# Universalsensor.net
KiCad netlist of a schematic drawn in EAGLE
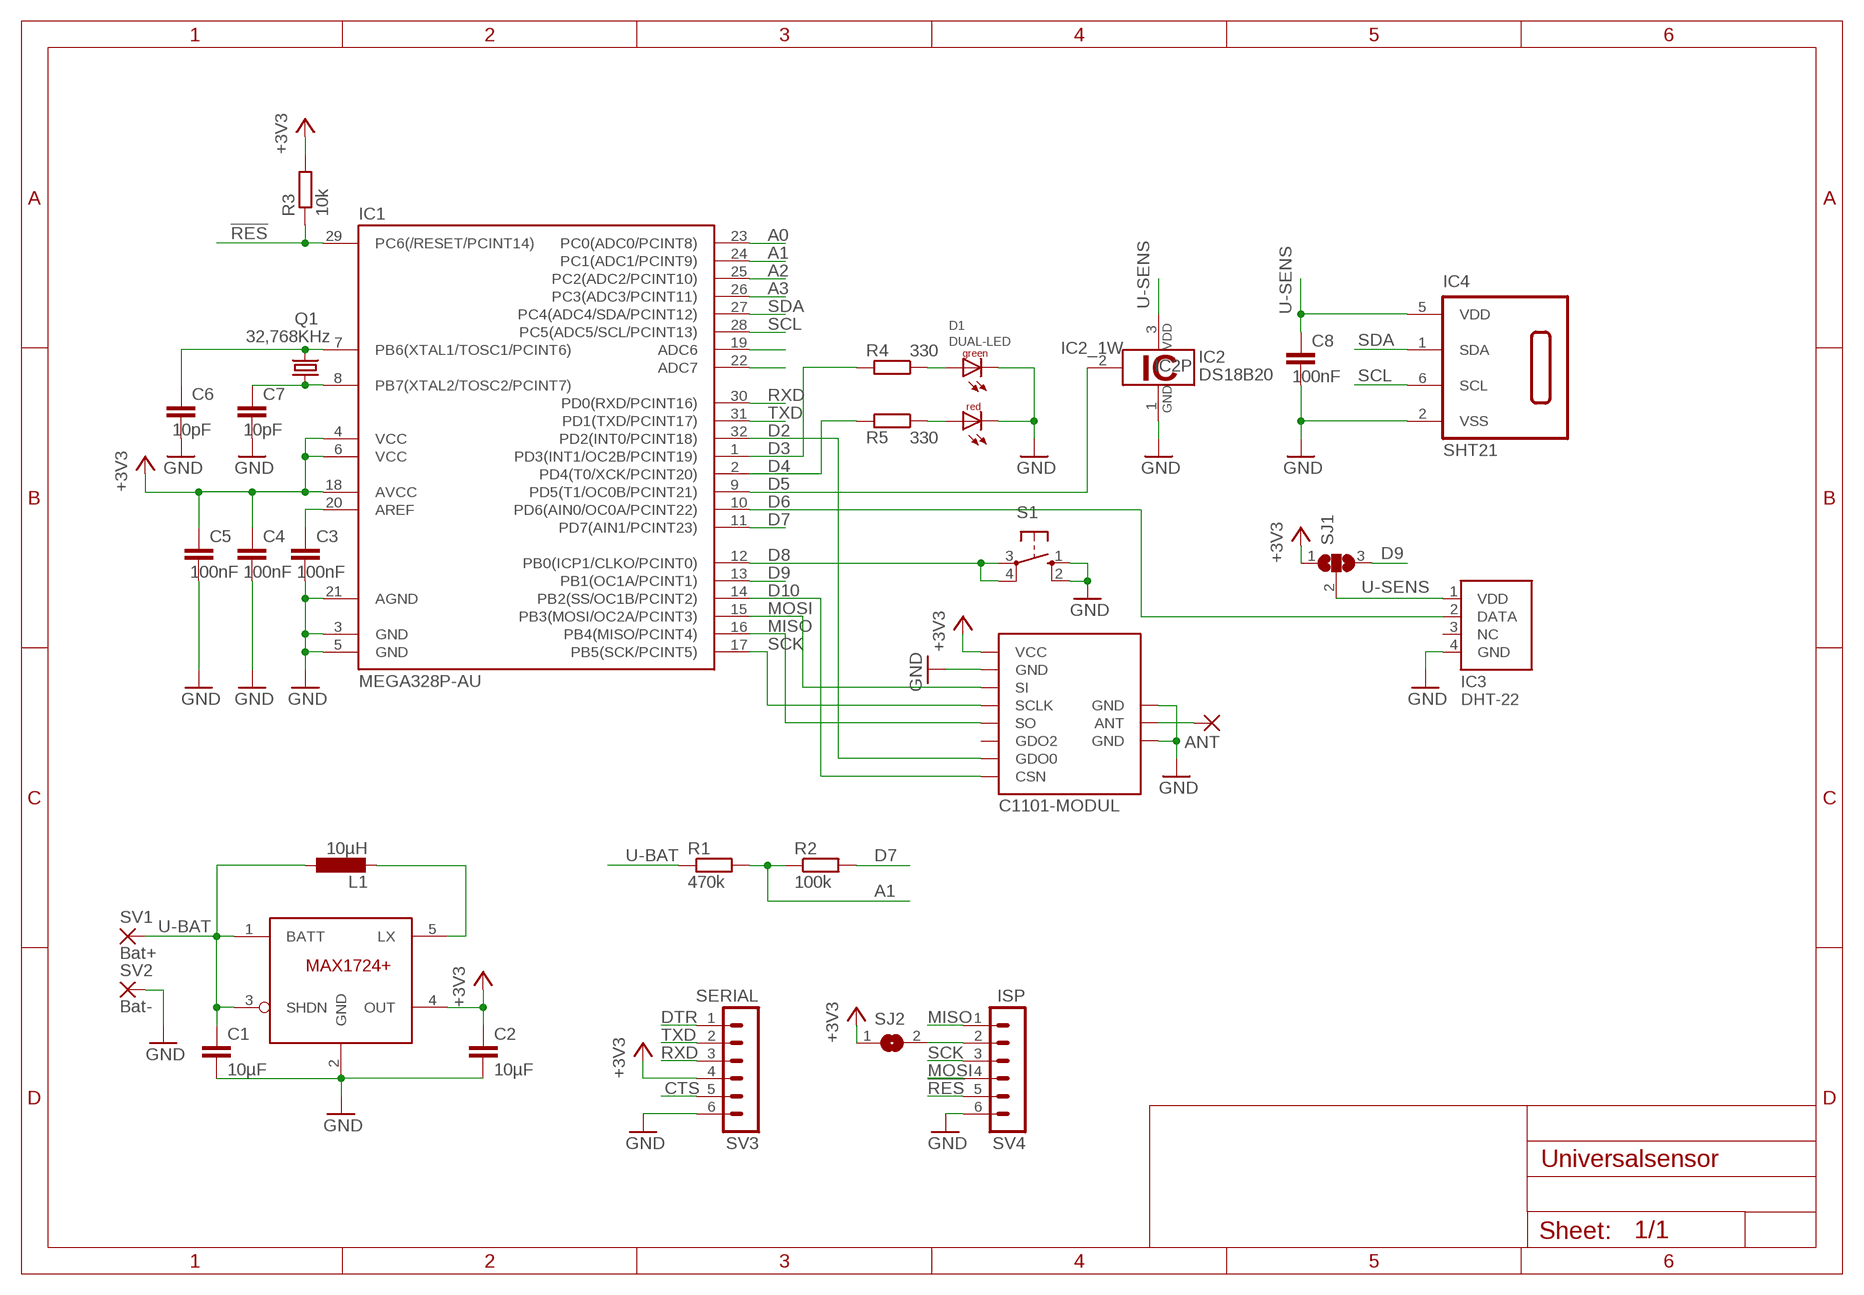
[diagram p0: schematic, sheet 1]

(export (version "E")
  (design (tool "Eeschema 10.0.6"))
  (components
    (comp (ref "ANT")
      (value "2,54/1,1")
      (footprint "eagle-import:2,54_1,1")
      (libsource (lib "eagle-import") (part "2,54/1,1"))
    )
    (comp (ref "C1")
      (value "10µF")
      (footprint "eagle-import:C0603K")
      (libsource (lib "eagle-import") (part "C-EUC0603K"))
    )
    (comp (ref "C2")
      (value "10µF")
      (footprint "eagle-import:C0603K")
      (libsource (lib "eagle-import") (part "C-EUC0603K"))
    )
    (comp (ref "C3")
      (value "100nF")
      (footprint "eagle-import:C0603K")
      (libsource (lib "eagle-import") (part "C-EUC0603K"))
    )
    (comp (ref "C4")
      (value "100nF")
      (footprint "eagle-import:C0603K")
      (libsource (lib "eagle-import") (part "C-EUC0603K"))
    )
    (comp (ref "C5")
      (value "100nF")
      (footprint "eagle-import:C0603K")
      (libsource (lib "eagle-import") (part "C-EUC0603K"))
    )
    (comp (ref "C6")
      (value "10pF")
      (footprint "eagle-import:C0603K")
      (libsource (lib "eagle-import") (part "C-EUC0603K"))
    )
    (comp (ref "C7")
      (value "10pF")
      (footprint "eagle-import:C0603K")
      (libsource (lib "eagle-import") (part "C-EUC0603K"))
    )
    (comp (ref "C8")
      (value "100nF")
      (footprint "eagle-import:C0603K")
      (libsource (lib "eagle-import") (part "C-EUC0603K"))
    )
    (comp (ref "D1")
      (value "DUAL-LED")
      (footprint "eagle-import:DUAL-LED")
      (libsource (lib "eagle-import") (part "DUAL-LED"))
    )
    (comp (ref "IC1")
      (value "MEGA328P-AU")
      (footprint "eagle-import:TQFP32-08")
      (libsource (lib "eagle-import") (part "MEGA48/88/168-AU"))
    )
    (comp (ref "IC2")
      (value "DS18B20")
      (footprint "eagle-import:TO92-")
      (libsource (lib "eagle-import") (part "DS18B20"))
    )
    (comp (ref "IC3")
      (value "DHT-22")
      (footprint "eagle-import:DHT-22-L")
      (libsource (lib "eagle-import") (part "DHT-22"))
    )
    (comp (ref "IC4")
      (value "SHT21")
      (footprint "eagle-import:DFN6_SHT")
      (libsource (lib "eagle-import") (part "SHT21"))
    )
    (comp (ref "IC5")
      (value "MAX1724")
      (footprint "eagle-import:SOT23-5L")
      (libsource (lib "eagle-import") (part "MAX1724"))
    )
    (comp (ref "L1")
      (value "10µH")
      (footprint "eagle-import:L3230M")
      (libsource (lib "eagle-import") (part "L-EUL3230M"))
    )
    (comp (ref "Q1")
      (value "32,768KHz")
      (footprint "eagle-import:OSCILLATOR_SMD")
      (libsource (lib "eagle-import") (part "OSCILLATOR_32KHZ"))
    )
    (comp (ref "R1")
      (value "470k")
      (footprint "eagle-import:R0805")
      (libsource (lib "eagle-import") (part "R-EU_R0805"))
    )
    (comp (ref "R2")
      (value "100k")
      (footprint "eagle-import:R0805")
      (libsource (lib "eagle-import") (part "R-EU_R0805"))
    )
    (comp (ref "R3")
      (value "10k")
      (footprint "eagle-import:R0805")
      (libsource (lib "eagle-import") (part "R-EU_R0805"))
    )
    (comp (ref "R4")
      (value "330")
      (footprint "eagle-import:R0805")
      (libsource (lib "eagle-import") (part "R-EU_R0805"))
    )
    (comp (ref "R5")
      (value "330")
      (footprint "eagle-import:R0805")
      (libsource (lib "eagle-import") (part "R-EU_R0805"))
    )
    (comp (ref "S1")
      (value "10-XX")
      (footprint "eagle-import:B3F-10XX")
      (fields (field (name "MPN") "B3F-1000"))
      (libsource (lib "eagle-import") (part "10-XX"))
    )
    (comp (ref "SJ1")
      (value "SJ2W")
      (footprint "eagle-import:SJ_2")
      (libsource (lib "eagle-import") (part "SJ2W"))
    )
    (comp (ref "SJ2") (value "SJ") (footprint "eagle-import:SJ") (libsource (lib "eagle-import") (part "SJ")))
    (comp (ref "SV1")
      (value "Bat+")
      (footprint "eagle-import:2,54_1,1")
      (libsource (lib "eagle-import") (part "2,54/1,1"))
    )
    (comp (ref "SV2")
      (value "Bat-")
      (footprint "eagle-import:2,54_1,1")
      (libsource (lib "eagle-import") (part "2,54/1,1"))
    )
    (comp (ref "SV3")
      (value "SERIAL")
      (footprint "eagle-import:MA06-1")
      (libsource (lib "eagle-import") (part "MA06-1"))
    )
    (comp (ref "SV4")
      (value "ISP")
      (footprint "eagle-import:MA06-1")
      (libsource (lib "eagle-import") (part "MA06-1"))
    )
    (comp (ref "U$2")
      (value "C1101-MODUL")
      (footprint "eagle-import:CC1101-MODUL")
      (libsource (lib "eagle-import") (part "C1101-MODUL"))
    )
  )
  (nets
    (net (code "1") (name "+3V3") (class "Default")
      (node (ref "C2") (pin "1") (pinfunction "1_1") (pintype "passive"))
      (node (ref "C4") (pin "1") (pinfunction "1_1") (pintype "passive"))
      (node (ref "C5") (pin "1") (pinfunction "1_1") (pintype "passive"))
      (node (ref "IC1") (pin "18") (pinfunction "AVCC_18") (pintype "passive"))
      (node (ref "IC1") (pin "4") (pinfunction "VCC_4") (pintype "power_in"))
      (node (ref "IC1") (pin "6") (pinfunction "VCC_6") (pintype "power_in"))
      (node (ref "IC5") (pin "4") (pinfunction "OUT_4") (pintype "output"))
      (node (ref "R3") (pin "2") (pinfunction "2_2") (pintype "passive"))
      (node (ref "SJ1") (pin "1") (pinfunction "1_1") (pintype "passive"))
      (node (ref "SJ2") (pin "1") (pinfunction "1_1") (pintype "passive"))
      (node (ref "SV3") (pin "4") (pinfunction "4_4") (pintype "passive"))
      (node (ref "U$2") (pin "VCC") (pinfunction "VCC_VCC") (pintype "power_in"))
    )
    (net (code "2") (name "/A0") (class "Default")
      (node (ref "IC1") (pin "23") (pinfunction "PC0(ADC0/PCINT8)_23") (pintype "bidirectional"))
    )
    (net (code "3") (name "/A1") (class "Default")
      (node (ref "IC1") (pin "24") (pinfunction "PC1(ADC1/PCINT9)_24") (pintype "bidirectional"))
      (node (ref "R1") (pin "2") (pinfunction "2_2") (pintype "passive"))
      (node (ref "R2") (pin "1") (pinfunction "1_1") (pintype "passive"))
    )
    (net (code "4") (name "/A2") (class "Default")
      (node (ref "IC1") (pin "25") (pinfunction "PC2(ADC2/PCINT10)_25") (pintype "bidirectional"))
    )
    (net (code "5") (name "/A3") (class "Default")
      (node (ref "IC1") (pin "26") (pinfunction "PC3(ADC3/PCINT11)_26") (pintype "bidirectional"))
    )
    (net (code "6") (name "/CTS") (class "Default")
      (node (ref "SV3") (pin "5") (pinfunction "5_5") (pintype "passive"))
    )
    (net (code "7") (name "/D2") (class "Default")
      (node (ref "IC1") (pin "32") (pinfunction "PD2(INT0/PCINT18)_32") (pintype "bidirectional"))
      (node (ref "U$2") (pin "GDO0") (pinfunction "GDO0_GDO0") (pintype "bidirectional"))
    )
    (net (code "8") (name "/D3") (class "Default")
      (node (ref "IC1") (pin "1") (pinfunction "PD3(INT1/OC2B/PCINT19)_1") (pintype "bidirectional"))
      (node (ref "R4") (pin "2") (pinfunction "2_2") (pintype "passive"))
    )
    (net (code "9") (name "/D4") (class "Default")
      (node (ref "IC1") (pin "2") (pinfunction "PD4(T0/XCK/PCINT20)_2") (pintype "bidirectional"))
      (node (ref "R5") (pin "2") (pinfunction "2_2") (pintype "passive"))
    )
    (net (code "10") (name "/D5") (class "Default")
      (node (ref "IC1") (pin "9") (pinfunction "PD5(T1/OC0B/PCINT21)_9") (pintype "bidirectional"))
      (node (ref "IC2") (pin "2") (pinfunction "1W_2") (pintype "power_in"))
    )
    (net (code "11") (name "/D6") (class "Default")
      (node (ref "IC1") (pin "10") (pinfunction "PD6(AIN0/OC0A/PCINT22)_10") (pintype "bidirectional"))
      (node (ref "IC3") (pin "2") (pinfunction "DATA_2") (pintype "bidirectional"))
    )
    (net (code "12") (name "/D7") (class "Default")
      (node (ref "IC1") (pin "11") (pinfunction "PD7(AIN1/PCINT23)_11") (pintype "bidirectional"))
      (node (ref "R2") (pin "2") (pinfunction "2_2") (pintype "passive"))
    )
    (net (code "13") (name "/D8") (class "Default")
      (node (ref "IC1") (pin "12") (pinfunction "PB0(ICP1/CLKO/PCINT0)_12") (pintype "bidirectional"))
      (node (ref "S1") (pin "3") (pinfunction "P_3") (pintype "passive"))
      (node (ref "S1") (pin "4") (pinfunction "P1_4") (pintype "passive"))
    )
    (net (code "14") (name "/D9") (class "Default")
      (node (ref "IC1") (pin "13") (pinfunction "PB1(OC1A/PCINT1)_13") (pintype "bidirectional"))
      (node (ref "SJ1") (pin "3") (pinfunction "3_3") (pintype "passive"))
    )
    (net (code "15") (name "/D10") (class "Default")
      (node (ref "IC1") (pin "14") (pinfunction "PB2(SS/OC1B/PCINT2)_14") (pintype "bidirectional"))
      (node (ref "U$2") (pin "CSN") (pinfunction "CSN_CSN") (pintype "bidirectional"))
    )
    (net (code "16") (name "/DTR") (class "Default")
      (node (ref "SV3") (pin "1") (pinfunction "1_1") (pintype "passive"))
    )
    (net (code "17") (name "/MISO") (class "Default")
      (node (ref "IC1") (pin "16") (pinfunction "PB4(MISO/PCINT4)_16") (pintype "bidirectional"))
      (node (ref "SV4") (pin "1") (pinfunction "1_1") (pintype "passive"))
      (node (ref "U$2") (pin "SO") (pinfunction "SO_SO") (pintype "bidirectional"))
    )
    (net (code "18") (name "/MOSI") (class "Default")
      (node (ref "IC1") (pin "15") (pinfunction "PB3(MOSI/OC2A/PCINT3)_15") (pintype "bidirectional"))
      (node (ref "SV4") (pin "4") (pinfunction "4_4") (pintype "passive"))
      (node (ref "U$2") (pin "SI") (pinfunction "SI_SI") (pintype "bidirectional"))
    )
    (net (code "19") (name "/RXD") (class "Default")
      (node (ref "IC1") (pin "30") (pinfunction "PD0(RXD/PCINT16)_30") (pintype "bidirectional"))
      (node (ref "SV3") (pin "3") (pinfunction "3_3") (pintype "passive"))
    )
    (net (code "20") (name "/SCK") (class "Default")
      (node (ref "IC1") (pin "17") (pinfunction "PB5(SCK/PCINT5)_17") (pintype "bidirectional"))
      (node (ref "SV4") (pin "3") (pinfunction "3_3") (pintype "passive"))
      (node (ref "U$2") (pin "SCLK") (pinfunction "SCLK_SCLK") (pintype "bidirectional"))
    )
    (net (code "21") (name "/SCL") (class "Default")
      (node (ref "IC1") (pin "28") (pinfunction "PC5(ADC5/SCL/PCINT13)_28") (pintype "bidirectional"))
      (node (ref "IC4") (pin "6") (pinfunction "SCL_6") (pintype "bidirectional"))
    )
    (net (code "22") (name "/SDA") (class "Default")
      (node (ref "IC1") (pin "27") (pinfunction "PC4(ADC4/SDA/PCINT12)_27") (pintype "bidirectional"))
      (node (ref "IC4") (pin "1") (pinfunction "SDA_1") (pintype "bidirectional"))
    )
    (net (code "23") (name "/TXD") (class "Default")
      (node (ref "IC1") (pin "31") (pinfunction "PD1(TXD/PCINT17)_31") (pintype "bidirectional"))
      (node (ref "SV3") (pin "2") (pinfunction "2_2") (pintype "passive"))
    )
    (net (code "24") (name "/U-BAT") (class "Default")
      (node (ref "C1") (pin "1") (pinfunction "1_1") (pintype "passive"))
      (node (ref "IC5") (pin "1") (pinfunction "BATT_1") (pintype "power_in"))
      (node (ref "IC5") (pin "3") (pinfunction "SHDN_3") (pintype "bidirectional"))
      (node (ref "L1") (pin "1") (pinfunction "1_1") (pintype "passive"))
      (node (ref "R1") (pin "1") (pinfunction "1_1") (pintype "passive"))
      (node (ref "SV1") (pin "1") (pinfunction "P_1") (pintype "passive"))
    )
    (net (code "25") (name "/U-SENS") (class "Default")
      (node (ref "C8") (pin "1") (pinfunction "1_1") (pintype "passive"))
      (node (ref "IC2") (pin "3") (pinfunction "VDD_3") (pintype "power_in"))
      (node (ref "IC3") (pin "1") (pinfunction "VDD_1") (pintype "power_in"))
      (node (ref "IC4") (pin "5") (pinfunction "VDD_5") (pintype "power_in"))
      (node (ref "SJ1") (pin "2") (pinfunction "2_2") (pintype "passive"))
    )
    (net (code "26") (name "/~{RES}") (class "Default")
      (node (ref "IC1") (pin "29") (pinfunction "PC6(/RESET/PCINT14)_29") (pintype "bidirectional"))
      (node (ref "R3") (pin "1") (pinfunction "1_1") (pintype "passive"))
      (node (ref "SV4") (pin "5") (pinfunction "5_5") (pintype "passive"))
    )
    (net (code "27") (name "GND") (class "Default")
      (node (ref "C1") (pin "2") (pinfunction "2_2") (pintype "passive"))
      (node (ref "C2") (pin "2") (pinfunction "2_2") (pintype "passive"))
      (node (ref "C3") (pin "2") (pinfunction "2_2") (pintype "passive"))
      (node (ref "C4") (pin "2") (pinfunction "2_2") (pintype "passive"))
      (node (ref "C5") (pin "2") (pinfunction "2_2") (pintype "passive"))
      (node (ref "C6") (pin "2") (pinfunction "2_2") (pintype "passive"))
      (node (ref "C7") (pin "2") (pinfunction "2_2") (pintype "passive"))
      (node (ref "C8") (pin "2") (pinfunction "2_2") (pintype "passive"))
      (node (ref "D1") (pin "P$3") (pinfunction "KG_P$3") (pintype "passive"))
      (node (ref "D1") (pin "P$4") (pinfunction "KR_P$4") (pintype "passive"))
      (node (ref "IC1") (pin "21") (pinfunction "AGND_21") (pintype "power_in"))
      (node (ref "IC1") (pin "3") (pinfunction "GND_3") (pintype "power_in"))
      (node (ref "IC1") (pin "5") (pinfunction "GND_5") (pintype "power_in"))
      (node (ref "IC2") (pin "1") (pinfunction "GND_1") (pintype "power_in"))
      (node (ref "IC3") (pin "4") (pinfunction "GND_4") (pintype "power_in"))
      (node (ref "IC4") (pin "2") (pinfunction "VSS_2") (pintype "power_in"))
      (node (ref "IC5") (pin "2") (pinfunction "GND_2") (pintype "power_in"))
      (node (ref "S1") (pin "1") (pinfunction "S_1") (pintype "passive"))
      (node (ref "S1") (pin "2") (pinfunction "S1_2") (pintype "passive"))
      (node (ref "SV2") (pin "1") (pinfunction "P_1") (pintype "passive"))
      (node (ref "SV3") (pin "6") (pinfunction "6_6") (pintype "passive"))
      (node (ref "SV4") (pin "6") (pinfunction "6_6") (pintype "passive"))
      (node (ref "U$2") (pin "GND@1") (pinfunction "GND_GND@1") (pintype "power_in"))
      (node (ref "U$2") (pin "GND@2") (pinfunction "GND_GND@2") (pintype "power_in"))
      (node (ref "U$2") (pin "GND@3") (pinfunction "GND_GND@3") (pintype "power_in"))
    )
    (net (code "28") (name "Net-(ANT-P)") (class "Default")
      (node (ref "ANT") (pin "1") (pinfunction "P_1") (pintype "passive"))
      (node (ref "U$2") (pin "ANT") (pinfunction "ANT_ANT") (pintype "bidirectional"))
    )
    (net (code "29") (name "Net-(D1-AG)") (class "Default")
      (node (ref "D1") (pin "P$1") (pinfunction "AG_P$1") (pintype "passive"))
      (node (ref "R4") (pin "1") (pinfunction "1_1") (pintype "passive"))
    )
    (net (code "30") (name "Net-(D1-AR)") (class "Default")
      (node (ref "D1") (pin "P$2") (pinfunction "AR_P$2") (pintype "passive"))
      (node (ref "R5") (pin "1") (pinfunction "1_1") (pintype "passive"))
    )
    (net (code "31") (name "Net-(IC1-AREF)") (class "Default")
      (node (ref "C3") (pin "1") (pinfunction "1_1") (pintype "passive"))
      (node (ref "IC1") (pin "20") (pinfunction "AREF_20") (pintype "passive"))
    )
    (net (code "32") (name "Net-(IC1-PB6(XTAL1{slash}TOSC1{slash}PCINT6))") (class "Default")
      (node (ref "C6") (pin "1") (pinfunction "1_1") (pintype "passive"))
      (node (ref "IC1") (pin "7") (pinfunction "PB6(XTAL1/TOSC1/PCINT6)_7") (pintype "bidirectional"))
      (node (ref "Q1") (pin "2") (pinfunction "2_2") (pintype "passive"))
    )
    (net (code "33") (name "Net-(IC1-PB7(XTAL2{slash}TOSC2{slash}PCINT7))") (class "Default")
      (node (ref "C7") (pin "1") (pinfunction "1_1") (pintype "passive"))
      (node (ref "IC1") (pin "8") (pinfunction "PB7(XTAL2/TOSC2/PCINT7)_8") (pintype "bidirectional"))
      (node (ref "Q1") (pin "1") (pinfunction "1_1") (pintype "passive"))
    )
    (net (code "34") (name "Net-(IC5-LX)") (class "Default")
      (node (ref "IC5") (pin "5") (pinfunction "LX_5") (pintype "input"))
      (node (ref "L1") (pin "2") (pinfunction "2_2") (pintype "passive"))
    )
    (net (code "35") (name "Net-(SJ2-Pad2)") (class "Default")
      (node (ref "SJ2") (pin "2") (pinfunction "2_2") (pintype "passive"))
      (node (ref "SV4") (pin "2") (pinfunction "2_2") (pintype "passive"))
    )
    (net (code "36") (name "unconnected-(IC1-ADC6-Pad19)") (class "Default")
      (node (ref "IC1") (pin "19") (pinfunction "ADC6_19") (pintype "passive"))
    )
    (net (code "37") (name "unconnected-(IC1-ADC7-Pad22)") (class "Default")
      (node (ref "IC1") (pin "22") (pinfunction "ADC7_22") (pintype "passive"))
    )
    (net (code "38") (name "unconnected-(IC3-NC-Pad3)") (class "Default")
      (node (ref "IC3") (pin "3") (pinfunction "NC_3") (pintype "bidirectional"))
    )
    (net (code "39") (name "unconnected-(U$2-PadGDO2)") (class "Default")
      (node (ref "U$2") (pin "GDO2") (pinfunction "GDO2_GDO2") (pintype "bidirectional"))
    )
  )
)
